# Dramco_UNO.net
KiCad netlist of a schematic drawn in EAGLE
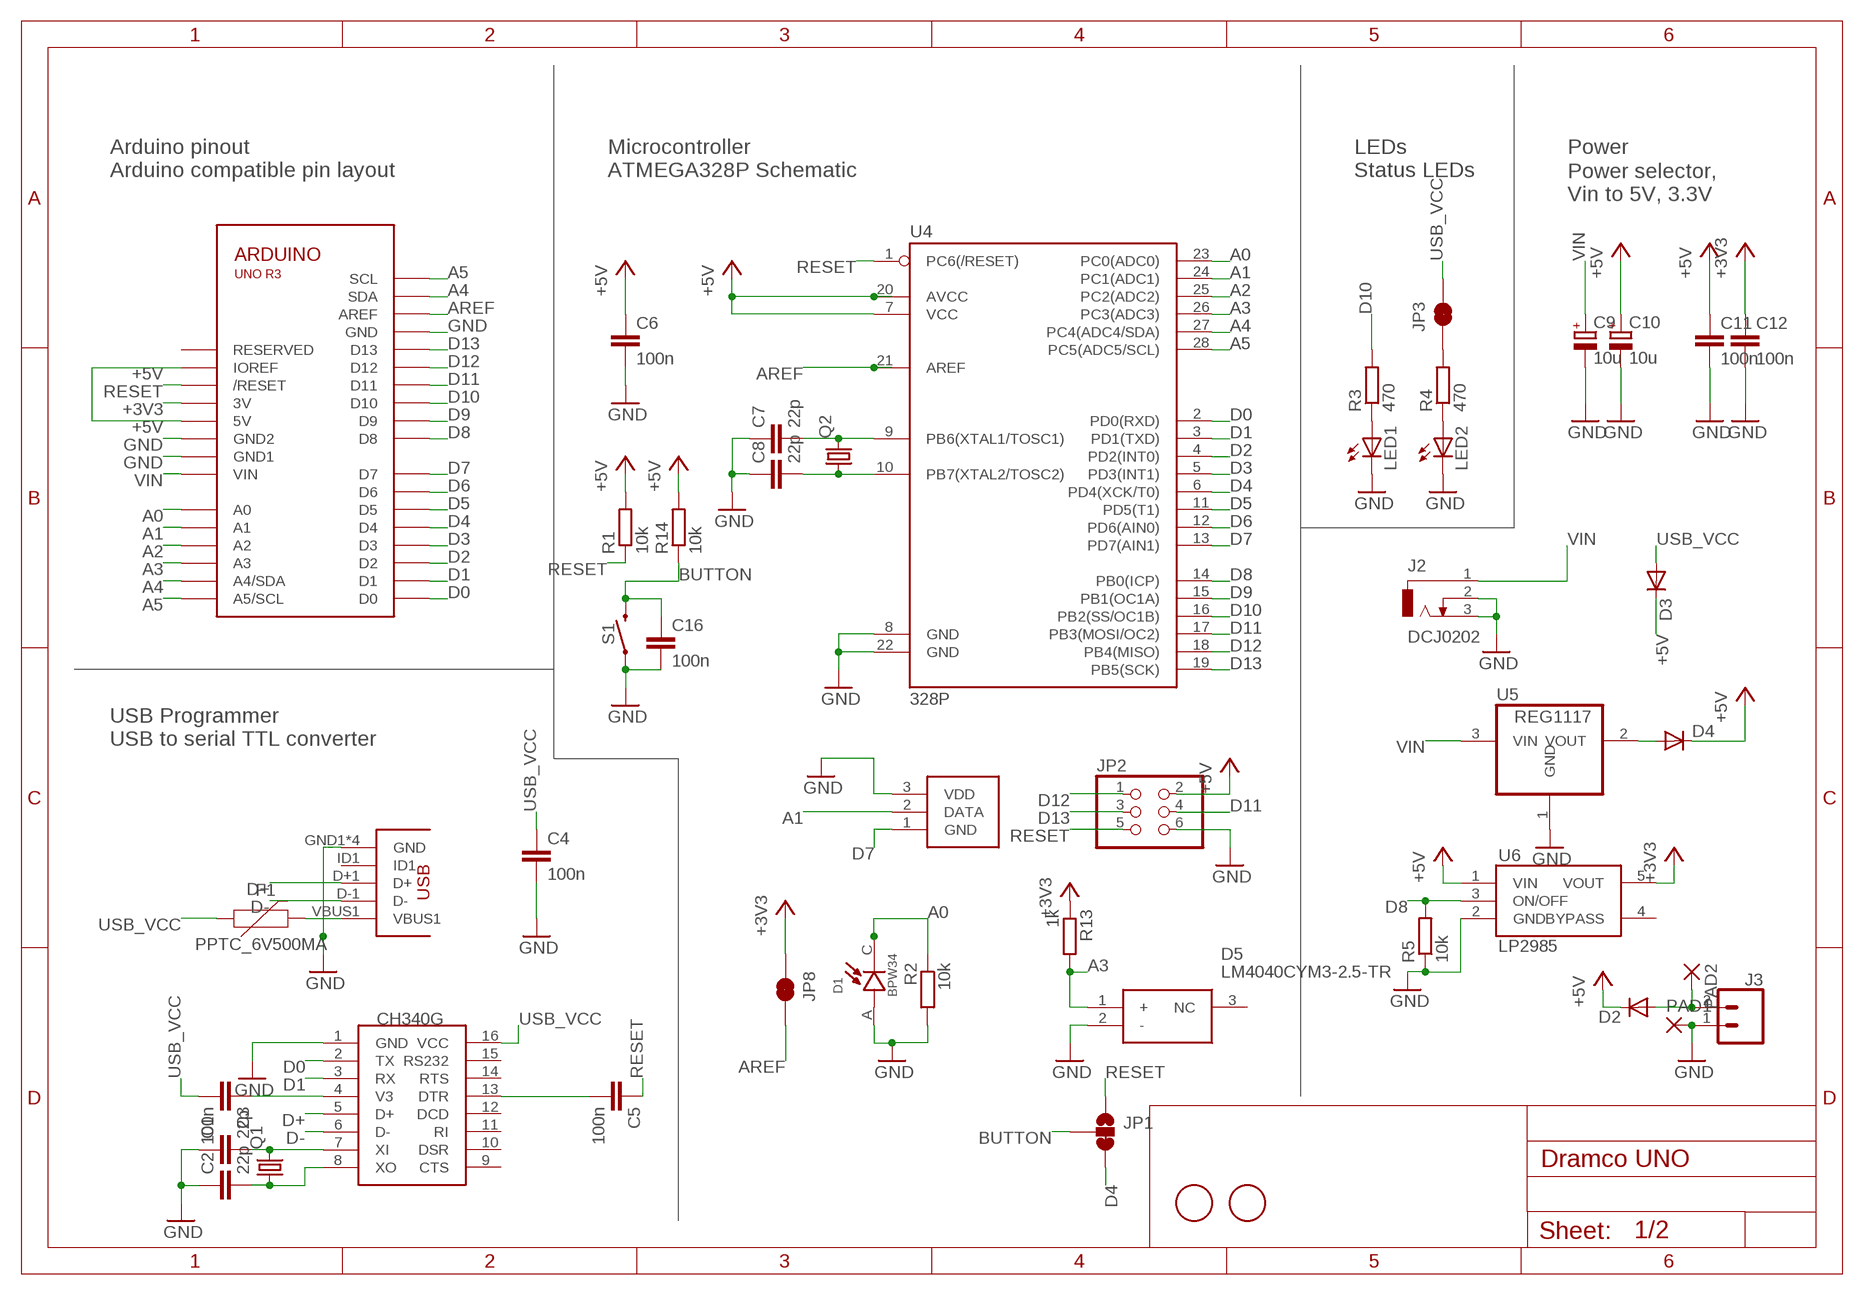
[diagram p0: schematic, sheet 1]
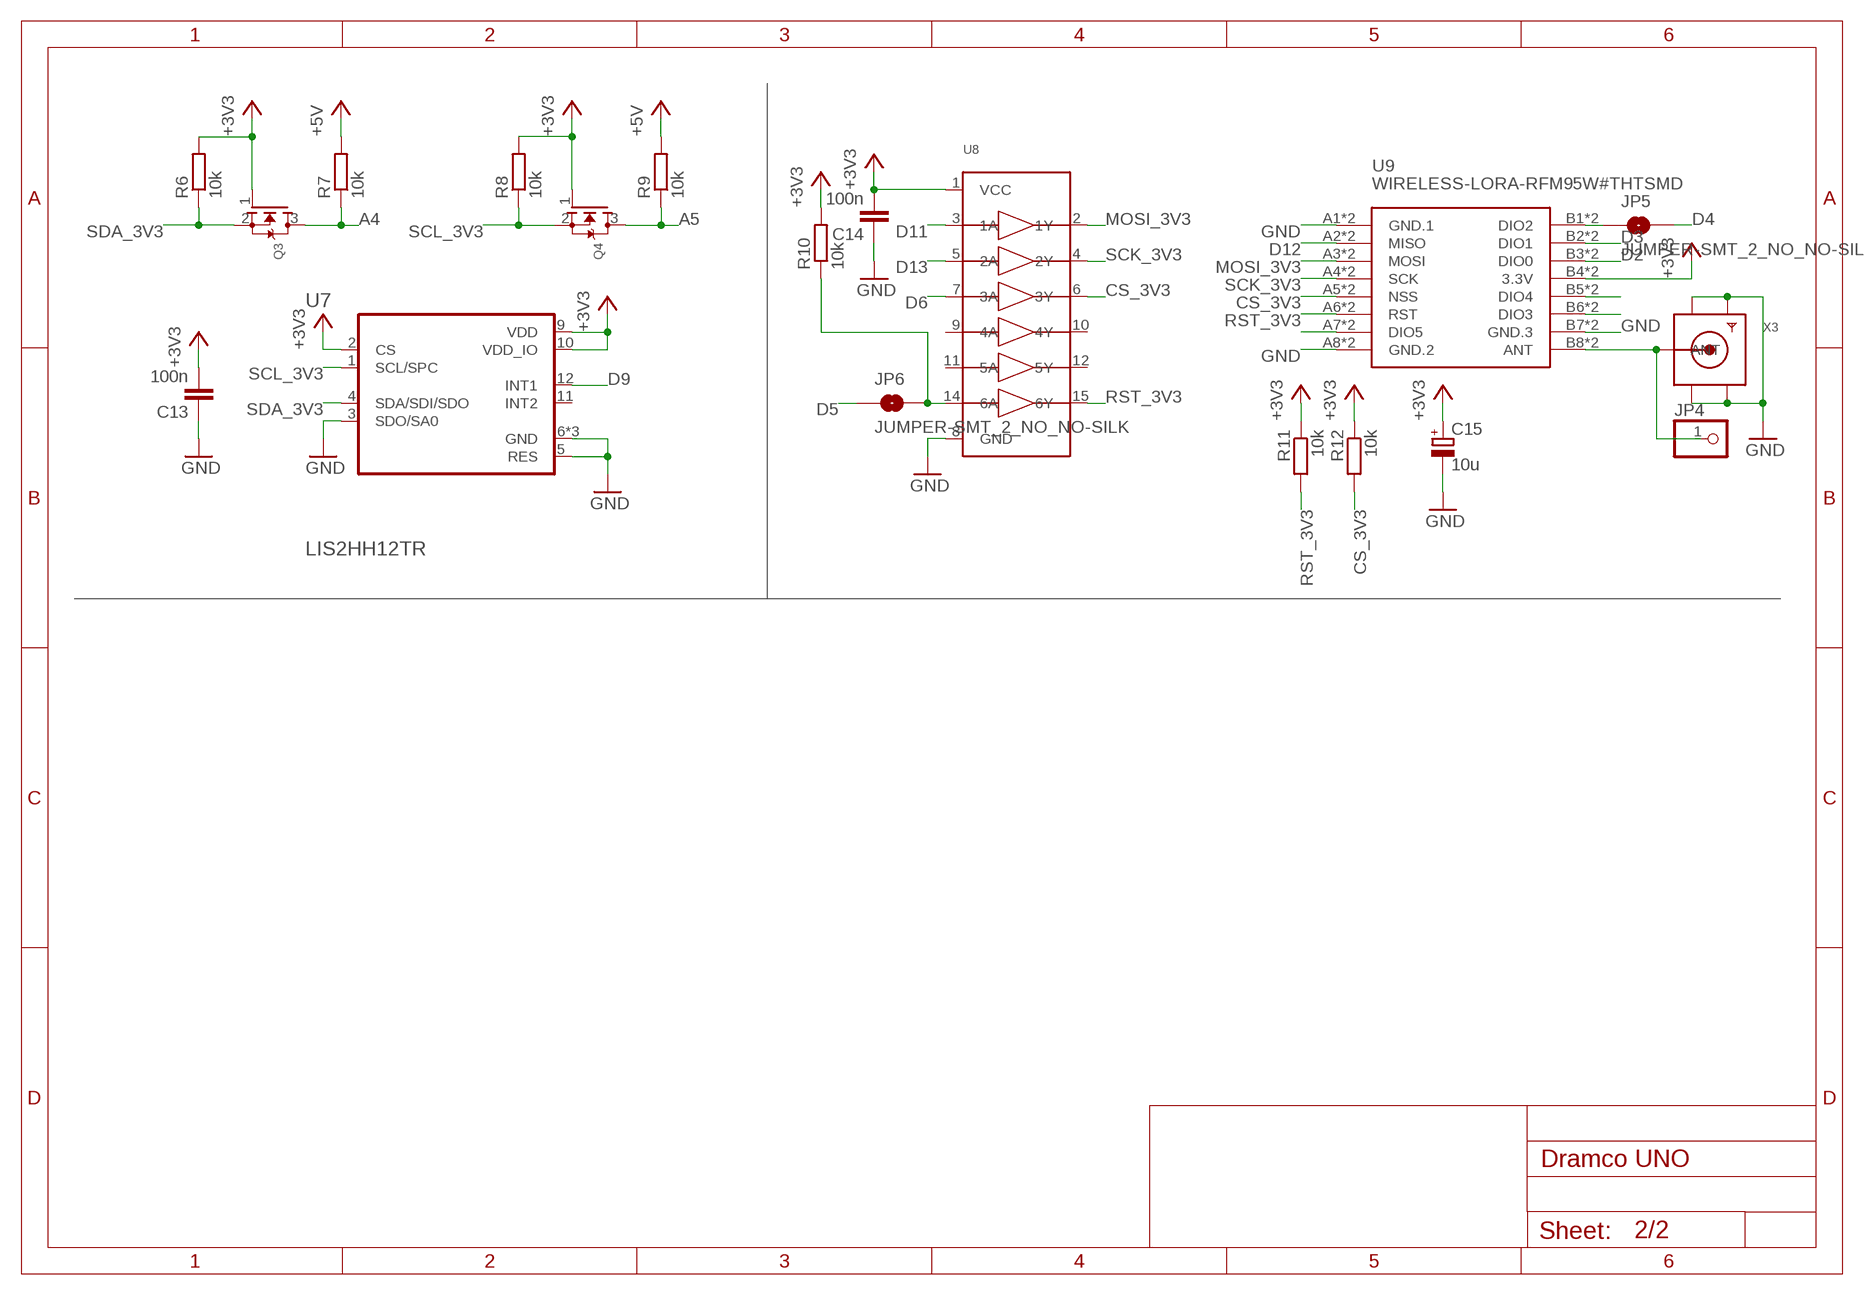
[diagram p1: schematic, sheet 2]

(export (version "E")
  (design (tool "Eeschema 10.0.6"))
  (components
    (comp (ref "C1")
      (value "22p")
      (footprint "eagle-import:C025-024X044")
      (libsource (lib "eagle-import") (part "resistor_C-EU025-024X044"))
    )
    (comp (ref "C2")
      (value "22p")
      (footprint "eagle-import:C025-024X044")
      (libsource (lib "eagle-import") (part "resistor_C-EU025-024X044"))
    )
    (comp (ref "C3")
      (value "100n")
      (footprint "eagle-import:C0603")
      (libsource (lib "eagle-import") (part "resistor_C-EUC0603"))
    )
    (comp (ref "C4")
      (value "100n")
      (footprint "eagle-import:C0603")
      (libsource (lib "eagle-import") (part "resistor_C-EUC0603"))
    )
    (comp (ref "C5")
      (value "100n")
      (footprint "eagle-import:C0603")
      (libsource (lib "eagle-import") (part "resistor_C-EUC0603"))
    )
    (comp (ref "C6")
      (value "100n")
      (footprint "eagle-import:C025-024X044")
      (libsource (lib "eagle-import") (part "resistor_C-EU025-024X044"))
    )
    (comp (ref "C7")
      (value "22p")
      (footprint "eagle-import:C025-024X044")
      (libsource (lib "eagle-import") (part "resistor_C-EU025-024X044"))
    )
    (comp (ref "C8")
      (value "22p")
      (footprint "eagle-import:C025-024X044")
      (libsource (lib "eagle-import") (part "resistor_C-EU025-024X044"))
    )
    (comp (ref "C9")
      (value "10u")
      (footprint "eagle-import:E2-4")
      (libsource (lib "eagle-import") (part "CPOL-EUE2-4"))
    )
    (comp (ref "C10")
      (value "10u")
      (footprint "eagle-import:E2-4")
      (libsource (lib "eagle-import") (part "CPOL-EUE2-4"))
    )
    (comp (ref "C11")
      (value "100n")
      (footprint "eagle-import:C0603")
      (libsource (lib "eagle-import") (part "C-EUC0603"))
    )
    (comp (ref "C12")
      (value "100n")
      (footprint "eagle-import:C0603")
      (libsource (lib "eagle-import") (part "C-EUC0603"))
    )
    (comp (ref "C16")
      (value "100n")
      (footprint "eagle-import:C0603")
      (libsource (lib "eagle-import") (part "resistor_C-EUC0603"))
    )
    (comp (ref "D1")
      (value "BPW34")
      (footprint "eagle-import:DIO_BPW34")
      (fields (field (name "MF") "Vishay Semiconductor"))
      (libsource (lib "eagle-import") (part "BPW34"))
    )
    (comp (ref "D2")
      (value "DIODE-D-5")
      (footprint "eagle-import:D-5")
      (libsource (lib "eagle-import") (part "DIODE-D-5"))
    )
    (comp (ref "D3")
      (value "DIODE-D-5")
      (footprint "eagle-import:D-5")
      (libsource (lib "eagle-import") (part "DIODE-D-5"))
    )
    (comp (ref "D4")
      (value "DIODE-D-5")
      (footprint "eagle-import:D-5")
      (libsource (lib "eagle-import") (part "DIODE-D-5"))
    )
    (comp (ref "D5")
      (value "LM4040CYM3-2.5-TR")
      (footprint "eagle-import:SOT95P235X111-3N")
      (fields (field (name "MOUSER_PART_NUMBER") "998-LM4040CYM3-2.5TR"))
      (libsource (lib "eagle-import") (part "LM4040CYM3-2.5-TR"))
    )
    (comp (ref "F1")
      (value "PPTC_6V500MA")
      (footprint "eagle-import:0805")
      (libsource (lib "eagle-import") (part "PPTC_6V500MA"))
    )
    (comp (ref "J1")
      (value "USB-AB")
      (footprint "eagle-import:USB-AB-MICRO-SMD_V02_BOSS")
      (libsource (lib "eagle-import") (part "USB-AB"))
    )
    (comp (ref "J2")
      (value "DCJ0202")
      (footprint "eagle-import:DCJ0202")
      (libsource (lib "eagle-import") (part "DCJ0202"))
    )
    (comp (ref "J3")
      (value "CONN_02JST-PTH-2")
      (footprint "eagle-import:JST-2-PTH")
      (libsource (lib "eagle-import") (part "CONN_02JST-PTH-2"))
    )
    (comp (ref "JP1")
      (value "JUMPER-SMT_3_1-NC_TRACE_SILK")
      (footprint "eagle-import:SMT-JUMPER_3_1-NC_TRACE_SILK")
      (libsource (lib "eagle-import") (part "JUMPER-SMT_3_1-NC_TRACE_SILK"))
    )
    (comp (ref "JP2")
      (value "PINHD-2X3")
      (footprint "eagle-import:2X03")
      (libsource (lib "eagle-import") (part "PINHD-2X3"))
    )
    (comp (ref "JP3")
      (value "JUMPER-SMT_2_NC_TRACE_NO-SILK")
      (footprint "eagle-import:SMT-JUMPER_2_NC_TRACE_NO-SILK")
      (libsource (lib "eagle-import") (part "JUMPER-SMT_2_NC_TRACE_NO-SILK"))
    )
    (comp (ref "JP8")
      (value "JUMPER-SMT_2_NC_TRACE_NO-SILK")
      (footprint "eagle-import:SMT-JUMPER_2_NC_TRACE_NO-SILK")
      (libsource (lib "eagle-import") (part "JUMPER-SMT_2_NC_TRACE_NO-SILK"))
    )
    (comp (ref "LED1")
      (value "LED5MM")
      (footprint "eagle-import:LED5MM")
      (libsource (lib "eagle-import") (part "LED5MM"))
    )
    (comp (ref "LED2")
      (value "LED5MM")
      (footprint "eagle-import:LED5MM")
      (libsource (lib "eagle-import") (part "LED5MM"))
    )
    (comp (ref "PAD1")
      (value "SMD2")
      (footprint "eagle-import:SMD1,27-2,54")
      (libsource (lib "eagle-import") (part "SMD2"))
    )
    (comp (ref "PAD2")
      (value "SMD2")
      (footprint "eagle-import:SMD1,27-2,54")
      (libsource (lib "eagle-import") (part "SMD2"))
    )
    (comp (ref "Q1")
      (value "CRYSTALHC49S")
      (footprint "eagle-import:HC49_S")
      (libsource (lib "eagle-import") (part "CRYSTALHC49S"))
    )
    (comp (ref "Q2")
      (value "CRYSTALHC49S")
      (footprint "eagle-import:HC49_S")
      (libsource (lib "eagle-import") (part "CRYSTALHC49S"))
    )
    (comp (ref "R1")
      (value "10k")
      (footprint "eagle-import:0204_7")
      (libsource (lib "eagle-import") (part "resistor_R-EU_0204/7"))
    )
    (comp (ref "R2")
      (value "10k")
      (footprint "eagle-import:0204_7")
      (libsource (lib "eagle-import") (part "resistor_R-EU_0204/7"))
    )
    (comp (ref "R3")
      (value "470")
      (footprint "eagle-import:0204_7")
      (libsource (lib "eagle-import") (part "resistor_R-EU_0204/7"))
    )
    (comp (ref "R4")
      (value "470")
      (footprint "eagle-import:0204_7")
      (libsource (lib "eagle-import") (part "resistor_R-EU_0204/7"))
    )
    (comp (ref "R5")
      (value "10k")
      (footprint "eagle-import:R0603")
      (libsource (lib "eagle-import") (part "R-EU_R0603"))
    )
    (comp (ref "R13")
      (value "1k")
      (footprint "eagle-import:R0603")
      (libsource (lib "eagle-import") (part "R-EU_R0603"))
    )
    (comp (ref "R14")
      (value "10k")
      (footprint "eagle-import:R0603")
      (libsource (lib "eagle-import") (part "R-EU_R0603"))
    )
    (comp (ref "S1")
      (value "MOMENTARY-SWITCH-SPST-PTH-6.0MM")
      (footprint "eagle-import:TACTILE_SWITCH_PTH_6.0MM")
      (libsource (lib "eagle-import") (part "MOMENTARY-SWITCH-SPST-PTH-6.0MM"))
    )
    (comp (ref "U1")
      (value "ARDUINOR3-DIMENSION")
      (footprint "eagle-import:ARDUINOR3")
      (libsource (lib "eagle-import") (part "ARDUINOR3-DIMENSION"))
    )
    (comp (ref "U2")
      (value "CH340G")
      (footprint "eagle-import:SOIC16")
      (libsource (lib "eagle-import") (part "CH340G"))
    )
    (comp (ref "U3")
      (value "DS18B20-TO92")
      (footprint "eagle-import:TO92-")
      (libsource (lib "eagle-import") (part "DS18B20-TO92"))
    )
    (comp (ref "U4")
      (value "328P")
      (footprint "eagle-import:DIP28")
      (libsource (lib "eagle-import") (part "ATMEGA328P_PDIP"))
    )
    (comp (ref "U5")
      (value "REG1117")
      (footprint "eagle-import:SOT223")
      (libsource (lib "eagle-import") (part "REG1117"))
    )
    (comp (ref "U6")
      (value "LP2985AIM5-3.3")
      (footprint "eagle-import:SOT25")
      (libsource (lib "eagle-import") (part "LP2985AIM5-3.3"))
    )
    (comp (ref "X1")
      (value "FIDUCIAL")
      (footprint "eagle-import:FIDUCIAL_1MM")
      (libsource (lib "eagle-import") (part "FIDUCIAL"))
    )
    (comp (ref "X2")
      (value "FIDUCIAL")
      (footprint "eagle-import:FIDUCIAL_1MM")
      (libsource (lib "eagle-import") (part "FIDUCIAL"))
    )
    (comp (ref "C13")
      (value "100n")
      (footprint "eagle-import:C0603")
      (libsource (lib "eagle-import") (part "C-EUC0603"))
    )
    (comp (ref "C14")
      (value "100n")
      (footprint "eagle-import:C0603")
      (libsource (lib "eagle-import") (part "C-EUC0603"))
    )
    (comp (ref "C15")
      (value "10u")
      (footprint "eagle-import:E2-4")
      (libsource (lib "eagle-import") (part "CPOL-EUE2-4"))
    )
    (comp (ref "JP4")
      (value "PINHD-1X1")
      (footprint "eagle-import:1X01")
      (libsource (lib "eagle-import") (part "PINHD-1X1"))
    )
    (comp (ref "JP5")
      (value "JUMPER-SMT_2_NO_NO-SILK")
      (footprint "eagle-import:SMT-JUMPER_2_NO_NO-SILK")
      (libsource (lib "eagle-import") (part "JUMPER-SMT_2_NO_NO-SILK"))
    )
    (comp (ref "JP6")
      (value "JUMPER-SMT_2_NO_NO-SILK")
      (footprint "eagle-import:SMT-JUMPER_2_NO_NO-SILK")
      (libsource (lib "eagle-import") (part "JUMPER-SMT_2_NO_NO-SILK"))
    )
    (comp (ref "Q3")
      (value "MOSFET-NREFLOW")
      (footprint "eagle-import:SOT23")
      (libsource (lib "eagle-import") (part "MOSFET-NREFLOW"))
    )
    (comp (ref "Q4")
      (value "MOSFET-NREFLOW")
      (footprint "eagle-import:SOT23")
      (libsource (lib "eagle-import") (part "MOSFET-NREFLOW"))
    )
    (comp (ref "R6")
      (value "10k")
      (footprint "eagle-import:R0603")
      (libsource (lib "eagle-import") (part "R-EU_R0603"))
    )
    (comp (ref "R7")
      (value "10k")
      (footprint "eagle-import:R0603")
      (libsource (lib "eagle-import") (part "R-EU_R0603"))
    )
    (comp (ref "R8")
      (value "10k")
      (footprint "eagle-import:R0603")
      (libsource (lib "eagle-import") (part "R-EU_R0603"))
    )
    (comp (ref "R9")
      (value "10k")
      (footprint "eagle-import:R0603")
      (libsource (lib "eagle-import") (part "R-EU_R0603"))
    )
    (comp (ref "R10")
      (value "10k")
      (footprint "eagle-import:R0603")
      (libsource (lib "eagle-import") (part "R-EU_R0603"))
    )
    (comp (ref "R11")
      (value "10k")
      (footprint "eagle-import:0204_7")
      (libsource (lib "eagle-import") (part "resistor_R-EU_0204/7"))
    )
    (comp (ref "R12")
      (value "10k")
      (footprint "eagle-import:0204_7")
      (libsource (lib "eagle-import") (part "resistor_R-EU_0204/7"))
    )
    (comp (ref "U7")
      (value "LIS2HH12TR")
      (footprint "eagle-import:PQFN50P200X200X100-12N")
      (fields (field (name "MF") "STMicroelectronics"))
      (libsource (lib "eagle-import") (part "LIS2HH12TR"))
    )
    (comp (ref "U8")
      (value "74HC4050DTSSOP")
      (footprint "eagle-import:TSSOP16")
      (libsource (lib "eagle-import") (part "74HC4050DTSSOP"))
    )
    (comp (ref "U9")
      (value "WIRELESS-LORA-RFM95W#THTSMD")
      (footprint "eagle-import:WIRELESS-LORA-RFM95W#THTSMD")
      (libsource (lib "eagle-import") (part "WIRELESS-LORA-RFM95W#THTSMD"))
    )
    (comp (ref "X3")
      (value "SMACONNECTOR_EDGE_UFL")
      (footprint "eagle-import:SMA_EDGELAUNCH_UFL")
      (libsource (lib "eagle-import") (part "SMACONNECTOR_EDGE_UFL"))
    )
  )
  (nets
    (net (code "1") (name "+3V3") (class "Default")
      (node (ref "C12") (pin "1") (pinfunction "1_1") (pintype "passive"))
      (node (ref "C13") (pin "2") (pinfunction "2_2") (pintype "passive"))
      (node (ref "C14") (pin "2") (pinfunction "2_2") (pintype "passive"))
      (node (ref "C15") (pin "+") (pinfunction "+_+") (pintype "passive"))
      (node (ref "JP8") (pin "1") (pinfunction "1_1") (pintype "passive"))
      (node (ref "Q3") (pin "1") (pinfunction "G_1") (pintype "bidirectional"))
      (node (ref "Q4") (pin "1") (pinfunction "G_1") (pintype "bidirectional"))
      (node (ref "R10") (pin "2") (pinfunction "2_2") (pintype "passive"))
      (node (ref "R11") (pin "1") (pinfunction "1_1") (pintype "passive"))
      (node (ref "R12") (pin "1") (pinfunction "1_1") (pintype "passive"))
      (node (ref "R13") (pin "1") (pinfunction "1_1") (pintype "passive"))
      (node (ref "R6") (pin "2") (pinfunction "2_2") (pintype "passive"))
      (node (ref "R8") (pin "2") (pinfunction "2_2") (pintype "passive"))
      (node (ref "U1") (pin "3V") (pinfunction "3V_3V") (pintype "power_in"))
      (node (ref "U6") (pin "5") (pinfunction "VOUT_5") (pintype "power_in"))
      (node (ref "U7") (pin "10") (pinfunction "VDD_IO_10") (pintype "power_in"))
      (node (ref "U7") (pin "2") (pinfunction "CS_2") (pintype "input"))
      (node (ref "U7") (pin "9") (pinfunction "VDD_9") (pintype "power_in"))
      (node (ref "U8") (pin "1") (pinfunction "VCC_1") (pintype "bidirectional"))
      (node (ref "U9") (pin "B12") (pinfunction "3.3V_B12") (pintype "power_in"))
      (node (ref "U9") (pin "B4") (pinfunction "3.3V_B4") (pintype "power_in"))
    )
    (net (code "2") (name "+5V") (class "Default")
      (node (ref "C10") (pin "+") (pinfunction "+_+") (pintype "passive"))
      (node (ref "C11") (pin "1") (pinfunction "1_1") (pintype "passive"))
      (node (ref "C6") (pin "1") (pinfunction "1_1") (pintype "passive"))
      (node (ref "D2") (pin "C") (pinfunction "C_C") (pintype "passive"))
      (node (ref "D3") (pin "C") (pinfunction "C_C") (pintype "passive"))
      (node (ref "D4") (pin "C") (pinfunction "C_C") (pintype "passive"))
      (node (ref "JP2") (pin "2") (pinfunction "2_2") (pintype "passive"))
      (node (ref "R1") (pin "2") (pinfunction "2_2") (pintype "passive"))
      (node (ref "R14") (pin "2") (pinfunction "2_2") (pintype "passive"))
      (node (ref "R7") (pin "2") (pinfunction "2_2") (pintype "passive"))
      (node (ref "R9") (pin "2") (pinfunction "2_2") (pintype "passive"))
      (node (ref "U1") (pin "5V") (pinfunction "5V_5V") (pintype "power_in"))
      (node (ref "U1") (pin "IOREF") (pinfunction "IOREF_IOREF") (pintype "output"))
      (node (ref "U4") (pin "20") (pinfunction "AVCC_20") (pintype "bidirectional"))
      (node (ref "U4") (pin "7") (pinfunction "VCC_7") (pintype "bidirectional"))
      (node (ref "U6") (pin "1") (pinfunction "VIN_1") (pintype "power_in"))
    )
    (net (code "3") (name "A0") (class "Default")
      (node (ref "D1") (pin "C") (pinfunction "C_C") (pintype "passive"))
      (node (ref "R2") (pin "1") (pinfunction "1_1") (pintype "passive"))
      (node (ref "U1") (pin "A0") (pinfunction "A0_A0") (pintype "bidirectional"))
      (node (ref "U4") (pin "23") (pinfunction "PC0(ADC0)_23") (pintype "bidirectional"))
    )
    (net (code "4") (name "A1") (class "Default")
      (node (ref "U1") (pin "A1") (pinfunction "A1_A1") (pintype "bidirectional"))
      (node (ref "U3") (pin "2") (pinfunction "DATA_2") (pintype "bidirectional"))
      (node (ref "U4") (pin "24") (pinfunction "PC1(ADC1)_24") (pintype "bidirectional"))
    )
    (net (code "5") (name "A2") (class "Default")
      (node (ref "U1") (pin "A2") (pinfunction "A2_A2") (pintype "bidirectional"))
      (node (ref "U4") (pin "25") (pinfunction "PC2(ADC2)_25") (pintype "bidirectional"))
    )
    (net (code "6") (name "A3") (class "Default")
      (node (ref "D5") (pin "1") (pinfunction "+_1") (pintype "bidirectional"))
      (node (ref "R13") (pin "2") (pinfunction "2_2") (pintype "passive"))
      (node (ref "U1") (pin "A3") (pinfunction "A3_A3") (pintype "bidirectional"))
      (node (ref "U4") (pin "26") (pinfunction "PC3(ADC3)_26") (pintype "bidirectional"))
    )
    (net (code "7") (name "A4") (class "Default")
      (node (ref "Q3") (pin "3") (pinfunction "D_3") (pintype "bidirectional"))
      (node (ref "R7") (pin "1") (pinfunction "1_1") (pintype "passive"))
      (node (ref "U1") (pin "A4") (pinfunction "A4/SDA_A4") (pintype "bidirectional"))
      (node (ref "U1") (pin "SDA") (pinfunction "SDA_SDA") (pintype "bidirectional"))
      (node (ref "U4") (pin "27") (pinfunction "PC4(ADC4/SDA)_27") (pintype "bidirectional"))
    )
    (net (code "8") (name "A5") (class "Default")
      (node (ref "Q4") (pin "3") (pinfunction "D_3") (pintype "bidirectional"))
      (node (ref "R9") (pin "1") (pinfunction "1_1") (pintype "passive"))
      (node (ref "U1") (pin "A5") (pinfunction "A5/SCL_A5") (pintype "bidirectional"))
      (node (ref "U1") (pin "SCL") (pinfunction "SCL_SCL") (pintype "bidirectional"))
      (node (ref "U4") (pin "28") (pinfunction "PC5(ADC5/SCL)_28") (pintype "bidirectional"))
    )
    (net (code "9") (name "AREF") (class "Default")
      (node (ref "JP8") (pin "2") (pinfunction "2_2") (pintype "passive"))
      (node (ref "U1") (pin "AREF") (pinfunction "AREF_AREF") (pintype "bidirectional"))
      (node (ref "U4") (pin "21") (pinfunction "AREF_21") (pintype "bidirectional"))
    )
    (net (code "10") (name "BUTTON") (class "Default")
      (node (ref "C16") (pin "1") (pinfunction "1_1") (pintype "passive"))
      (node (ref "JP1") (pin "2") (pinfunction "2_2") (pintype "passive"))
      (node (ref "R14") (pin "1") (pinfunction "1_1") (pintype "passive"))
      (node (ref "S1") (pin "3") (pinfunction "2_3") (pintype "passive"))
    )
    (net (code "11") (name "BYPASS") (class "Default")
      (node (ref "U6") (pin "4") (pinfunction "BYPASS_4") (pintype "power_in"))
    )
    (net (code "12") (name "CS_3V3") (class "Default")
      (node (ref "R12") (pin "2") (pinfunction "2_2") (pintype "passive"))
      (node (ref "U8") (pin "6") (pinfunction "3Y_6") (pintype "bidirectional"))
      (node (ref "U9") (pin "A13") (pinfunction "NSS_A13") (pintype "bidirectional"))
      (node (ref "U9") (pin "A5") (pinfunction "NSS_A5") (pintype "bidirectional"))
    )
    (net (code "13") (name "D+") (class "Default")
      (node (ref "J1") (pin "D+1") (pinfunction "D+_D+1") (pintype "bidirectional"))
      (node (ref "U2") (pin "5") (pinfunction "D+_5") (pintype "bidirectional"))
    )
    (net (code "14") (name "D-") (class "Default")
      (node (ref "J1") (pin "D-1") (pinfunction "D-_D-1") (pintype "bidirectional"))
      (node (ref "U2") (pin "6") (pinfunction "D-_6") (pintype "bidirectional"))
    )
    (net (code "15") (name "D0") (class "Default")
      (node (ref "U1") (pin "D0") (pinfunction "D0_D0") (pintype "bidirectional"))
      (node (ref "U2") (pin "2") (pinfunction "TX_2") (pintype "bidirectional"))
      (node (ref "U4") (pin "2") (pinfunction "PD0(RXD)_2") (pintype "bidirectional"))
    )
    (net (code "16") (name "D1") (class "Default")
      (node (ref "U1") (pin "D1") (pinfunction "D1_D1") (pintype "bidirectional"))
      (node (ref "U2") (pin "3") (pinfunction "RX_3") (pintype "bidirectional"))
      (node (ref "U4") (pin "3") (pinfunction "PD1(TXD)_3") (pintype "bidirectional"))
    )
    (net (code "17") (name "D2") (class "Default")
      (node (ref "U1") (pin "D2") (pinfunction "D2_D2") (pintype "bidirectional"))
      (node (ref "U4") (pin "4") (pinfunction "PD2(INT0)_4") (pintype "bidirectional"))
      (node (ref "U9") (pin "B11") (pinfunction "DIO0_B11") (pintype "bidirectional"))
      (node (ref "U9") (pin "B3") (pinfunction "DIO0_B3") (pintype "bidirectional"))
    )
    (net (code "18") (name "D3") (class "Default")
      (node (ref "U1") (pin "D3") (pinfunction "D3_D3") (pintype "bidirectional"))
      (node (ref "U4") (pin "5") (pinfunction "PD3(INT1)_5") (pintype "bidirectional"))
      (node (ref "U9") (pin "B10") (pinfunction "DIO1_B10") (pintype "bidirectional"))
      (node (ref "U9") (pin "B2") (pinfunction "DIO1_B2") (pintype "bidirectional"))
    )
    (net (code "19") (name "D4") (class "Default")
      (node (ref "JP1") (pin "3") (pinfunction "3_3") (pintype "passive"))
      (node (ref "JP5") (pin "2") (pinfunction "2_2") (pintype "passive"))
      (node (ref "U1") (pin "D4") (pinfunction "D4_D4") (pintype "bidirectional"))
      (node (ref "U4") (pin "6") (pinfunction "PD4(XCK/T0)_6") (pintype "bidirectional"))
    )
    (net (code "20") (name "D5") (class "Default")
      (node (ref "JP6") (pin "1") (pinfunction "1_1") (pintype "passive"))
      (node (ref "U1") (pin "D5") (pinfunction "D5_D5") (pintype "bidirectional"))
      (node (ref "U4") (pin "11") (pinfunction "PD5(T1)_11") (pintype "bidirectional"))
    )
    (net (code "21") (name "D6") (class "Default")
      (node (ref "U1") (pin "D6") (pinfunction "D6_D6") (pintype "bidirectional"))
      (node (ref "U4") (pin "12") (pinfunction "PD6(AIN0)_12") (pintype "bidirectional"))
      (node (ref "U8") (pin "7") (pinfunction "3A_7") (pintype "bidirectional"))
    )
    (net (code "22") (name "D7") (class "Default")
      (node (ref "U1") (pin "D7") (pinfunction "D7_D7") (pintype "bidirectional"))
      (node (ref "U3") (pin "1") (pinfunction "GND_1") (pintype "bidirectional"))
      (node (ref "U4") (pin "13") (pinfunction "PD7(AIN1)_13") (pintype "bidirectional"))
    )
    (net (code "23") (name "D8") (class "Default")
      (node (ref "R5") (pin "2") (pinfunction "2_2") (pintype "passive"))
      (node (ref "U1") (pin "D8") (pinfunction "D8_D8") (pintype "bidirectional"))
      (node (ref "U4") (pin "14") (pinfunction "PB0(ICP)_14") (pintype "bidirectional"))
      (node (ref "U6") (pin "3") (pinfunction "ON/OFF_3") (pintype "input"))
    )
    (net (code "24") (name "D9") (class "Default")
      (node (ref "U1") (pin "D9") (pinfunction "D9_D9") (pintype "bidirectional"))
      (node (ref "U4") (pin "15") (pinfunction "PB1(OC1A)_15") (pintype "bidirectional"))
      (node (ref "U7") (pin "12") (pinfunction "INT1_12") (pintype "output"))
    )
    (net (code "25") (name "D10") (class "Default")
      (node (ref "R3") (pin "2") (pinfunction "2_2") (pintype "passive"))
      (node (ref "U1") (pin "D10") (pinfunction "D10_D10") (pintype "bidirectional"))
      (node (ref "U4") (pin "16") (pinfunction "PB2(SS/OC1B)_16") (pintype "bidirectional"))
    )
    (net (code "26") (name "D11") (class "Default")
      (node (ref "JP2") (pin "4") (pinfunction "4_4") (pintype "passive"))
      (node (ref "U1") (pin "D11") (pinfunction "D11_D11") (pintype "bidirectional"))
      (node (ref "U4") (pin "17") (pinfunction "PB3(MOSI/OC2)_17") (pintype "bidirectional"))
      (node (ref "U8") (pin "3") (pinfunction "1A_3") (pintype "bidirectional"))
    )
    (net (code "27") (name "D12") (class "Default")
      (node (ref "JP2") (pin "1") (pinfunction "1_1") (pintype "passive"))
      (node (ref "U1") (pin "D12") (pinfunction "D12_D12") (pintype "bidirectional"))
      (node (ref "U4") (pin "18") (pinfunction "PB4(MISO)_18") (pintype "bidirectional"))
      (node (ref "U9") (pin "A10") (pinfunction "MISO_A10") (pintype "bidirectional"))
      (node (ref "U9") (pin "A2") (pinfunction "MISO_A2") (pintype "bidirectional"))
    )
    (net (code "28") (name "D13") (class "Default")
      (node (ref "JP2") (pin "3") (pinfunction "3_3") (pintype "passive"))
      (node (ref "U1") (pin "D13") (pinfunction "D13_D13") (pintype "bidirectional"))
      (node (ref "U4") (pin "19") (pinfunction "PB5(SCK)_19") (pintype "bidirectional"))
      (node (ref "U8") (pin "5") (pinfunction "2A_5") (pintype "bidirectional"))
    )
    (net (code "29") (name "GND") (class "Default")
      (node (ref "C1") (pin "1") (pinfunction "1_1") (pintype "passive"))
      (node (ref "C10") (pin "-") (pinfunction "-_-") (pintype "passive"))
      (node (ref "C11") (pin "2") (pinfunction "2_2") (pintype "passive"))
      (node (ref "C12") (pin "2") (pinfunction "2_2") (pintype "passive"))
      (node (ref "C13") (pin "1") (pinfunction "1_1") (pintype "passive"))
      (node (ref "C14") (pin "1") (pinfunction "1_1") (pintype "passive"))
      (node (ref "C15") (pin "-") (pinfunction "-_-") (pintype "passive"))
      (node (ref "C16") (pin "2") (pinfunction "2_2") (pintype "passive"))
      (node (ref "C2") (pin "1") (pinfunction "1_1") (pintype "passive"))
      (node (ref "C4") (pin "2") (pinfunction "2_2") (pintype "passive"))
      (node (ref "C6") (pin "2") (pinfunction "2_2") (pintype "passive"))
      (node (ref "C7") (pin "1") (pinfunction "1_1") (pintype "passive"))
      (node (ref "C8") (pin "1") (pinfunction "1_1") (pintype "passive"))
      (node (ref "C9") (pin "-") (pinfunction "-_-") (pintype "passive"))
      (node (ref "D1") (pin "A") (pinfunction "A_A") (pintype "passive"))
      (node (ref "D5") (pin "2") (pinfunction "-_2") (pintype "bidirectional"))
      (node (ref "J1") (pin "GND1") (pinfunction "GND_GND1") (pintype "bidirectional"))
      (node (ref "J1") (pin "P$1") (pinfunction "GND_P$1") (pintype "bidirectional"))
      (node (ref "J1") (pin "P$2") (pinfunction "GND_P$2") (pintype "bidirectional"))
      (node (ref "J1") (pin "P$3") (pinfunction "GND_P$3") (pintype "bidirectional"))
      (node (ref "J2") (pin "2") (pinfunction "2_2") (pintype "passive"))
      (node (ref "J2") (pin "3") (pinfunction "3_3") (pintype "passive"))
      (node (ref "J3") (pin "1") (pinfunction "1_1") (pintype "passive"))
      (node (ref "JP2") (pin "6") (pinfunction "6_6") (pintype "passive"))
      (node (ref "LED1") (pin "K") (pinfunction "C_K") (pintype "passive"))
      (node (ref "LED2") (pin "K") (pinfunction "C_K") (pintype "passive"))
      (node (ref "PAD1") (pin "1") (pinfunction "P_1") (pintype "passive"))
      (node (ref "R2") (pin "2") (pinfunction "2_2") (pintype "passive"))
      (node (ref "R5") (pin "1") (pinfunction "1_1") (pintype "passive"))
      (node (ref "S1") (pin "1") (pinfunction "1_1") (pintype "passive"))
      (node (ref "U1") (pin "GND") (pinfunction "GND_GND") (pintype "power_in"))
      (node (ref "U1") (pin "GND1") (pinfunction "GND1_GND1") (pintype "power_in"))
      (node (ref "U1") (pin "GND2") (pinfunction "GND2_GND2") (pintype "power_in"))
      (node (ref "U2") (pin "1") (pinfunction "GND_1") (pintype "bidirectional"))
      (node (ref "U3") (pin "3") (pinfunction "VDD_3") (pintype "bidirectional"))
      (node (ref "U4") (pin "22") (pinfunction "GND_22") (pintype "bidirectional"))
      (node (ref "U4") (pin "8") (pinfunction "GND_8") (pintype "bidirectional"))
      (node (ref "U5") (pin "1") (pinfunction "GND_1") (pintype "power_in"))
      (node (ref "U6") (pin "2") (pinfunction "GND_2") (pintype "power_in"))
      (node (ref "U7") (pin "3") (pinfunction "SDO/SA0_3") (pintype "bidirectional"))
      (node (ref "U7") (pin "5") (pinfunction "RES_5") (pintype "power_in"))
      (node (ref "U7") (pin "6") (pinfunction "GND_6") (pintype "power_in"))
      (node (ref "U7") (pin "7") (pinfunction "GND_7") (pintype "power_in"))
      (node (ref "U7") (pin "8") (pinfunction "GND_8") (pintype "power_in"))
      (node (ref "U8") (pin "8") (pinfunction "GND_8") (pintype "bidirectional"))
      (node (ref "U9") (pin "A1") (pinfunction "GND.1_A1") (pintype "power_in"))
      (node (ref "U9") (pin "A16") (pinfunction "GND.2_A16") (pintype "power_in"))
      (node (ref "U9") (pin "A8") (pinfunction "GND.2_A8") (pintype "power_in"))
      (node (ref "U9") (pin "A9") (pinfunction "GND.1_A9") (pintype "power_in"))
      (node (ref "U9") (pin "B15") (pinfunction "GND.3_B15") (pintype "power_in"))
      (node (ref "U9") (pin "B7") (pinfunction "GND.3_B7") (pintype "power_in"))
      (node (ref "X3") (pin "GND@1") (pinfunction "GND1_GND@1") (pintype "power_in"))
      (node (ref "X3") (pin "GND@2") (pinfunction "GND2_GND@2") (pintype "power_in"))
      (node (ref "X3") (pin "GND@3") (pinfunction "GND3_GND@3") (pintype "power_in"))
      (node (ref "X3") (pin "GND@4") (pinfunction "GND4_GND@4") (pintype "power_in"))
    )
    (net (code "30") (name "MOSI_3V3") (class "Default")
      (node (ref "U8") (pin "2") (pinfunction "1Y_2") (pintype "bidirectional"))
      (node (ref "U9") (pin "A11") (pinfunction "MOSI_A11") (pintype "bidirectional"))
      (node (ref "U9") (pin "A3") (pinfunction "MOSI_A3") (pintype "bidirectional"))
    )
    (net (code "31") (name "Net-(F1-Pad2)") (class "Default")
      (node (ref "F1") (pin "2") (pinfunction "2_2") (pintype "bidirectional"))
      (node (ref "J1") (pin "VBUS1") (pinfunction "VBUS1_VBUS1") (pintype "bidirectional"))
    )
    (net (code "32") (name "Net-(JP3-Pad1)") (class "Default")
      (node (ref "JP3") (pin "1") (pinfunction "1_1") (pintype "passive"))
      (node (ref "R4") (pin "2") (pinfunction "2_2") (pintype "passive"))
    )
    (net (code "33") (name "Net-(JP5-Pad1)") (class "Default")
      (node (ref "JP5") (pin "1") (pinfunction "1_1") (pintype "passive"))
      (node (ref "U9") (pin "B1") (pinfunction "DIO2_B1") (pintype "bidirectional"))
      (node (ref "U9") (pin "B9") (pinfunction "DIO2_B9") (pintype "bidirectional"))
    )
    (net (code "34") (name "Net-(LED1-PadA)") (class "Default")
      (node (ref "LED1") (pin "A") (pinfunction "A_A") (pintype "passive"))
      (node (ref "R3") (pin "1") (pinfunction "1_1") (pintype "passive"))
    )
    (net (code "35") (name "Net-(LED2-PadA)") (class "Default")
      (node (ref "LED2") (pin "A") (pinfunction "A_A") (pintype "passive"))
      (node (ref "R4") (pin "1") (pinfunction "1_1") (pintype "passive"))
    )
    (net (code "36") (name "Net-(PAD2-P)") (class "Default")
      (node (ref "D2") (pin "A") (pinfunction "A_A") (pintype "passive"))
      (node (ref "J3") (pin "2") (pinfunction "2_2") (pintype "passive"))
      (node (ref "PAD2") (pin "1") (pinfunction "P_1") (pintype "passive"))
    )
    (net (code "37") (name "Net-(U2-DTR)") (class "Default")
      (node (ref "C5") (pin "2") (pinfunction "2_2") (pintype "passive"))
      (node (ref "U2") (pin "13") (pinfunction "DTR_13") (pintype "bidirectional"))
    )
    (net (code "38") (name "Net-(U2-V3)") (class "Default")
      (node (ref "C3") (pin "1") (pinfunction "1_1") (pintype "passive"))
      (node (ref "U2") (pin "4") (pinfunction "V3_4") (pintype "bidirectional"))
    )
    (net (code "39") (name "Net-(U2-XI)") (class "Default")
      (node (ref "C1") (pin "2") (pinfunction "2_2") (pintype "passive"))
      (node (ref "Q1") (pin "2") (pinfunction "2_2") (pintype "passive"))
      (node (ref "U2") (pin "7") (pinfunction "XI_7") (pintype "bidirectional"))
    )
    (net (code "40") (name "Net-(U2-XO)") (class "Default")
      (node (ref "C2") (pin "2") (pinfunction "2_2") (pintype "passive"))
      (node (ref "Q1") (pin "1") (pinfunction "1_1") (pintype "passive"))
      (node (ref "U2") (pin "8") (pinfunction "XO_8") (pintype "bidirectional"))
    )
    (net (code "41") (name "Net-(U4-PB6(XTAL1{slash}TOSC1))") (class "Default")
      (node (ref "C7") (pin "2") (pinfunction "2_2") (pintype "passive"))
      (node (ref "Q2") (pin "2") (pinfunction "2_2") (pintype "passive"))
      (node (ref "U4") (pin "9") (pinfunction "PB6(XTAL1/TOSC1)_9") (pintype "bidirectional"))
    )
    (net (code "42") (name "Net-(U4-PB7(XTAL2{slash}TOSC2))") (class "Default")
      (node (ref "C8") (pin "2") (pinfunction "2_2") (pintype "passive"))
      (node (ref "Q2") (pin "1") (pinfunction "1_1") (pintype "passive"))
      (node (ref "U4") (pin "10") (pinfunction "PB7(XTAL2/TOSC2)_10") (pintype "bidirectional"))
    )
    (net (code "43") (name "Net-(U5-VOUT)") (class "Default")
      (node (ref "D4") (pin "A") (pinfunction "A_A") (pintype "passive"))
      (node (ref "U5") (pin "2") (pinfunction "VOUT_2") (pintype "output"))
    )
    (net (code "44") (name "Net-(U8-6A)") (class "Default")
      (node (ref "JP6") (pin "2") (pinfunction "2_2") (pintype "passive"))
      (node (ref "R10") (pin "1") (pinfunction "1_1") (pintype "passive"))
      (node (ref "U8") (pin "14") (pinfunction "6A_14") (pintype "bidirectional"))
    )
    (net (code "45") (name "Net-(U9-DIO3-PadB14)") (class "Default")
      (node (ref "U9") (pin "B14") (pinfunction "DIO3_B14") (pintype "bidirectional"))
      (node (ref "U9") (pin "B6") (pinfunction "DIO3_B6") (pintype "bidirectional"))
    )
    (net (code "46") (name "Net-(U9-DIO4-PadB13)") (class "Default")
      (node (ref "U9") (pin "B13") (pinfunction "DIO4_B13") (pintype "bidirectional"))
      (node (ref "U9") (pin "B5") (pinfunction "DIO4_B5") (pintype "bidirectional"))
    )
    (net (code "47") (name "Net-(U9-DIO5-PadA15)") (class "Default")
      (node (ref "U9") (pin "A15") (pinfunction "DIO5_A15") (pintype "bidirectional"))
      (node (ref "U9") (pin "A7") (pinfunction "DIO5_A7") (pintype "bidirectional"))
    )
    (net (code "48") (name "Net-(X3-ANT)") (class "Default")
      (node (ref "JP4") (pin "1") (pinfunction "1_1") (pintype "passive"))
      (node (ref "U9") (pin "B16") (pinfunction "ANT_B16") (pintype "passive"))
      (node (ref "U9") (pin "B8") (pinfunction "ANT_B8") (pintype "passive"))
      (node (ref "X3") (pin "P") (pinfunction "ANT_P") (pintype "bidirectional"))
    )
    (net (code "49") (name "RESET") (class "Default")
      (node (ref "C5") (pin "1") (pinfunction "1_1") (pintype "passive"))
      (node (ref "JP1") (pin "1") (pinfunction "1_1") (pintype "passive"))
      (node (ref "JP2") (pin "5") (pinfunction "5_5") (pintype "passive"))
      (node (ref "R1") (pin "1") (pinfunction "1_1") (pintype "passive"))
      (node (ref "U1") (pin "RESET") (pinfunction "/RESET_RESET") (pintype "bidirectional"))
      (node (ref "U4") (pin "1") (pinfunction "PC6(/RESET)_1") (pintype "bidirectional"))
    )
    (net (code "50") (name "RST_3V3") (class "Default")
      (node (ref "R11") (pin "2") (pinfunction "2_2") (pintype "passive"))
      (node (ref "U8") (pin "15") (pinfunction "6Y_15") (pintype "bidirectional"))
      (node (ref "U9") (pin "A14") (pinfunction "RST_A14") (pintype "bidirectional"))
      (node (ref "U9") (pin "A6") (pinfunction "RST_A6") (pintype "bidirectional"))
    )
    (net (code "51") (name "SCK_3V3") (class "Default")
      (node (ref "U8") (pin "4") (pinfunction "2Y_4") (pintype "bidirectional"))
      (node (ref "U9") (pin "A12") (pinfunction "SCK_A12") (pintype "bidirectional"))
      (node (ref "U9") (pin "A4") (pinfunction "SCK_A4") (pintype "bidirectional"))
    )
    (net (code "52") (name "SCL_3V3") (class "Default")
      (node (ref "Q4") (pin "2") (pinfunction "S_2") (pintype "bidirectional"))
      (node (ref "R8") (pin "1") (pinfunction "1_1") (pintype "passive"))
      (node (ref "U7") (pin "1") (pinfunction "SCL/SPC_1") (pintype "input"))
    )
    (net (code "53") (name "SDA_3V3") (class "Default")
      (node (ref "Q3") (pin "2") (pinfunction "S_2") (pintype "bidirectional"))
      (node (ref "R6") (pin "1") (pinfunction "1_1") (pintype "passive"))
      (node (ref "U7") (pin "4") (pinfunction "SDA/SDI/SDO_4") (pintype "bidirectional"))
    )
    (net (code "54") (name "USB_VCC") (class "Default")
      (node (ref "C3") (pin "2") (pinfunction "2_2") (pintype "passive"))
      (node (ref "C4") (pin "1") (pinfunction "1_1") (pintype "passive"))
      (node (ref "D3") (pin "A") (pinfunction "A_A") (pintype "passive"))
      (node (ref "F1") (pin "1") (pinfunction "1_1") (pintype "bidirectional"))
      (node (ref "JP3") (pin "2") (pinfunction "2_2") (pintype "passive"))
      (node (ref "U2") (pin "16") (pinfunction "VCC_16") (pintype "bidirectional"))
    )
    (net (code "55") (name "VIN") (class "Default")
      (node (ref "C9") (pin "+") (pinfunction "+_+") (pintype "passive"))
      (node (ref "J2") (pin "1") (pinfunction "1_1") (pintype "passive"))
      (node (ref "U1") (pin "VIN") (pinfunction "VIN_VIN") (pintype "power_in"))
      (node (ref "U5") (pin "3") (pinfunction "VIN_3") (pintype "input"))
    )
    (net (code "56") (name "unconnected-(D5-NC-Pad3)") (class "Default")
      (node (ref "D5") (pin "3") (pinfunction "NC_3") (pintype "no_connect"))
    )
    (net (code "57") (name "unconnected-(J1-PadID1)") (class "Default")
      (node (ref "J1") (pin "ID1") (pinfunction "ID1_ID1") (pintype "bidirectional"))
    )
    (net (code "58") (name "unconnected-(U1-PadRESERVED)") (class "Default")
      (node (ref "U1") (pin "RESERVED") (pinfunction "RESERVED_RESERVED") (pintype "no_connect"))
    )
    (net (code "59") (name "unconnected-(U2-CTS-Pad9)") (class "Default")
      (node (ref "U2") (pin "9") (pinfunction "CTS_9") (pintype "bidirectional"))
    )
    (net (code "60") (name "unconnected-(U2-DCD-Pad12)") (class "Default")
      (node (ref "U2") (pin "12") (pinfunction "DCD_12") (pintype "bidirectional"))
    )
    (net (code "61") (name "unconnected-(U2-DSR-Pad10)") (class "Default")
      (node (ref "U2") (pin "10") (pinfunction "DSR_10") (pintype "bidirectional"))
    )
    (net (code "62") (name "unconnected-(U2-RI-Pad11)") (class "Default")
      (node (ref "U2") (pin "11") (pinfunction "RI_11") (pintype "bidirectional"))
    )
    (net (code "63") (name "unconnected-(U2-RS232-Pad15)") (class "Default")
      (node (ref "U2") (pin "15") (pinfunction "RS232_15") (pintype "bidirectional"))
    )
    (net (code "64") (name "unconnected-(U2-RTS-Pad14)") (class "Default")
      (node (ref "U2") (pin "14") (pinfunction "RTS_14") (pintype "bidirectional"))
    )
    (net (code "65") (name "unconnected-(U7-INT2-Pad11)") (class "Default")
      (node (ref "U7") (pin "11") (pinfunction "INT2_11") (pintype "output"))
    )
    (net (code "66") (name "unconnected-(U8-4A-Pad9)") (class "Default")
      (node (ref "U8") (pin "9") (pinfunction "4A_9") (pintype "bidirectional"))
    )
    (net (code "67") (name "unconnected-(U8-4Y-Pad10)") (class "Default")
      (node (ref "U8") (pin "10") (pinfunction "4Y_10") (pintype "bidirectional"))
    )
    (net (code "68") (name "unconnected-(U8-5A-Pad11)") (class "Default")
      (node (ref "U8") (pin "11") (pinfunction "5A_11") (pintype "bidirectional"))
    )
    (net (code "69") (name "unconnected-(U8-5Y-Pad12)") (class "Default")
      (node (ref "U8") (pin "12") (pinfunction "5Y_12") (pintype "bidirectional"))
    )
  )
)
